# Main.net
KiCad netlist of a schematic drawn in Altium Designer
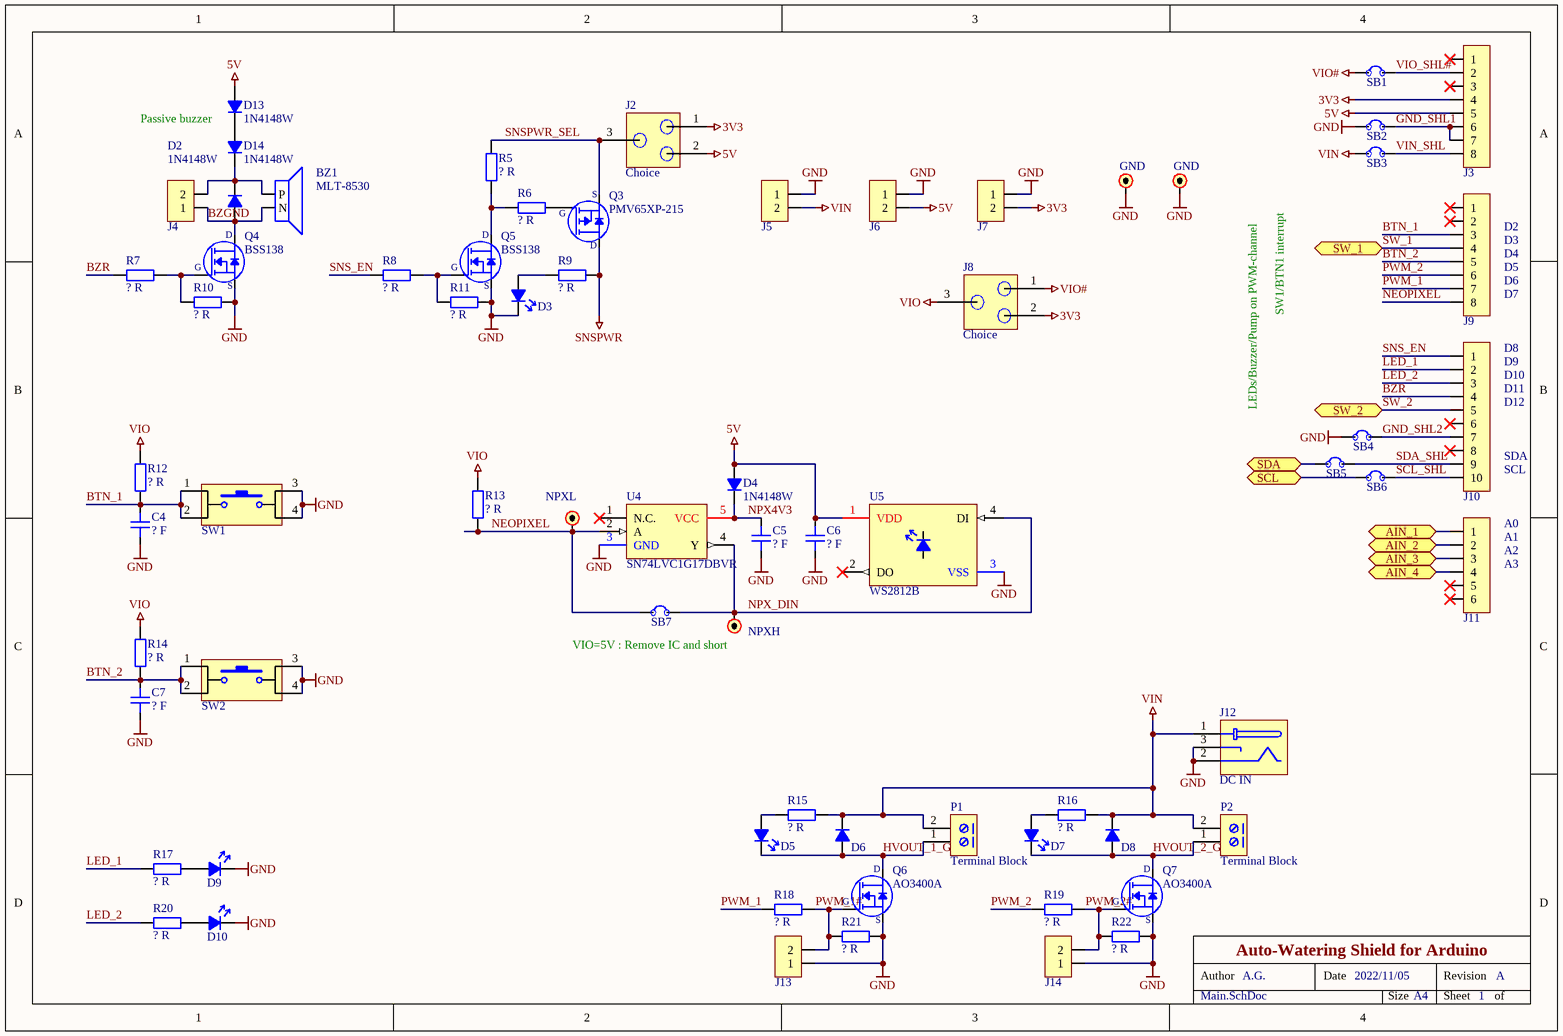
[diagram p0: Main.SchDoc]

(export (version "E")
  (design (tool "Eeschema 10.0.6"))
  (components
    (comp (ref "BZ1")
      (value "MLT-8530")
      (footprint "MLT-8530")
      (description "Magnetic Buzzer SMD 8.5x3.3 Passive 2.5V~4.5V")
      (fields (field (name "MANUFACTURER") "Jiangsu Huaneng Elec"))
      (libsource (lib "Buzzer") (part "MLT-8530"))
    )
    (comp (ref "C4")
      (value "? F")
      (footprint "0603C_RF_M")
      (description "Capacitor")
      (fields (field (name "TOLERANCE") "?") (field (name "MANUFACTURER") "Generic Brand"))
      (libsource (lib "AG.Generic") (part "C"))
    )
    (comp (ref "C5")
      (value "? F")
      (footprint "0603C_RF_M")
      (description "Capacitor")
      (fields (field (name "TOLERANCE") "?") (field (name "MANUFACTURER") "Generic Brand"))
      (libsource (lib "AG.Generic") (part "C"))
    )
    (comp (ref "C6")
      (value "? F")
      (footprint "0603C_RF_M")
      (description "Capacitor")
      (fields (field (name "TOLERANCE") "?") (field (name "MANUFACTURER") "Generic Brand"))
      (libsource (lib "AG.Generic") (part "C"))
    )
    (comp (ref "C7")
      (value "? F")
      (footprint "0603C_RF_M")
      (description "Capacitor")
      (fields (field (name "TOLERANCE") "?") (field (name "MANUFACTURER") "Generic Brand"))
      (libsource (lib "AG.Generic") (part "C"))
    )
    (comp (ref "D2")
      (value "1N4148W")
      (footprint "D_SOD-123")
      (description "DIODE GEN PURP 100V 300MA SOD123")
      (fields (field (name "SIMILAR PART") "BAV16W") (field (name "MANUFACTURER") "Diodes Incorporated"))
      (libsource (lib "Diode") (part "1N4148W"))
    )
    (comp (ref "D3")
      (value "Unspecified")
      (footprint "0805LED_RF_M")
      (description "LED")
      (fields (field (name "MANUFACTURER") "Generic Brand"))
      (libsource (lib "AG.Generic") (part "LED"))
    )
    (comp (ref "D4")
      (value "1N4148W")
      (footprint "D_SOD-123")
      (description "DIODE GEN PURP 100V 300MA SOD123")
      (fields (field (name "SIMILAR PART") "BAV16W") (field (name "MANUFACTURER") "Diodes Incorporated"))
      (libsource (lib "Diode") (part "1N4148W"))
    )
    (comp (ref "D5")
      (value "Unspecified")
      (footprint "0805LED_RF_M")
      (description "LED")
      (fields (field (name "MANUFACTURER") "Generic Brand"))
      (libsource (lib "AG.Generic") (part "LED"))
    )
    (comp (ref "D6")
      (value "D")
      (footprint "ONSEMI_DO214AC_RF_M")
      (description "Diode (Rectifier)")
      (fields (field (name "MANUFACTURER") "Generic Brand"))
      (libsource (lib "AG.Generic") (part "D"))
    )
    (comp (ref "D7")
      (value "Unspecified")
      (footprint "0805LED_RF_M")
      (description "LED")
      (fields (field (name "MANUFACTURER") "Generic Brand"))
      (libsource (lib "AG.Generic") (part "LED"))
    )
    (comp (ref "D8")
      (value "D")
      (footprint "ONSEMI_DO214AC_RF_M")
      (description "Diode (Rectifier)")
      (fields (field (name "MANUFACTURER") "Generic Brand"))
      (libsource (lib "AG.Generic") (part "D"))
    )
    (comp (ref "D9")
      (value "Unspecified")
      (footprint "0805LED_RF_M")
      (description "LED")
      (fields (field (name "MANUFACTURER") "Generic Brand"))
      (libsource (lib "AG.Generic") (part "LED"))
    )
    (comp (ref "D10")
      (value "Unspecified")
      (footprint "0805LED_RF_M")
      (description "LED")
      (fields (field (name "MANUFACTURER") "Generic Brand"))
      (libsource (lib "AG.Generic") (part "LED"))
    )
    (comp (ref "D13")
      (value "1N4148W")
      (footprint "D_SOD-123")
      (description "DIODE GEN PURP 100V 300MA SOD123")
      (fields (field (name "SIMILAR PART") "BAV16W") (field (name "MANUFACTURER") "Diodes Incorporated"))
      (libsource (lib "Diode") (part "1N4148W"))
    )
    (comp (ref "D14")
      (value "1N4148W")
      (footprint "D_SOD-123")
      (description "DIODE GEN PURP 100V 300MA SOD123")
      (fields (field (name "SIMILAR PART") "BAV16W") (field (name "MANUFACTURER") "Diodes Incorporated"))
      (libsource (lib "Diode") (part "1N4148W"))
    )
    (comp (ref "J2")
      (value "Choice")
      (footprint "AG.Misc:CHOICE_R0805_TR")
      (libsource (lib "AG.Misc") (part "Choice"))
    )
    (comp (ref "J3")
      (value "PINHDR-8P1")
      (footprint "PINHDR-8P1-2.54")
      (description "Pin Header Single Row 8 Positions")
      (libsource (lib "AG.Connectors") (part "PINHDR-8P1"))
    )
    (comp (ref "J4")
      (value "PINHDR-2P1")
      (footprint "HEADER-2.54-2P1")
      (description "Pin Header Single Row 2 Positions")
      (libsource (lib "") (part "PINHDR-2P1_1"))
    )
    (comp (ref "J5")
      (value "PINHDR-2P1")
      (footprint "HEADER-2.54-2P1")
      (description "Pin Header Single Row 2 Positions")
      (libsource (lib "AG.Connectors") (part "PINHDR-2P1"))
    )
    (comp (ref "J6")
      (value "PINHDR-2P1")
      (footprint "HEADER-2.54-2P1")
      (description "Pin Header Single Row 2 Positions")
      (libsource (lib "AG.Connectors") (part "PINHDR-2P1"))
    )
    (comp (ref "J7")
      (value "PINHDR-2P1")
      (footprint "HEADER-2.54-2P1")
      (description "Pin Header Single Row 2 Positions")
      (libsource (lib "AG.Connectors") (part "PINHDR-2P1"))
    )
    (comp (ref "J8")
      (value "Choice")
      (footprint "AG.Misc:CHOICE_R0805_TR")
      (libsource (lib "AG.Misc") (part "Choice"))
    )
    (comp (ref "J9")
      (value "PINHDR-8P1")
      (footprint "PINHDR-8P1-2.54")
      (description "Pin Header Single Row 8 Positions")
      (libsource (lib "AG.Connectors") (part "PINHDR-8P1"))
    )
    (comp (ref "J10")
      (value "PINHDR-10P1")
      (footprint "AG.Connectors:HEADER-2.54-10P1")
      (description "Generic Pin Header 10x1")
      (libsource (lib "AG.Connectors") (part "PINHDR-10P1"))
    )
    (comp (ref "J11")
      (value "PINHDR-6P1")
      (footprint "HEADER-2.54-6P1")
      (description "Pin Header Single Row 6 Positions")
      (libsource (lib "AG.Connectors") (part "PINHDR-6P1"))
    )
    (comp (ref "J12")
      (value "DC IN")
      (footprint "CON JACK PWR 2.5mm PJ-002BH - duplicate")
      (description "CONN PWR JACK 2.5X5.5MM SOLDER")
      (fields (field (name "MANUFACTURER") "CUI Devices") (field (name "PARTNO") "CP-002BH-ND"))
      (libsource (lib "AG.Connectors") (part "PJ-002BH"))
    )
    (comp (ref "J13")
      (value "PINHDR-2P1")
      (footprint "HEADER-2.54-2P1")
      (description "Pin Header Single Row 2 Positions")
      (libsource (lib "") (part "PINHDR-2P1_1"))
    )
    (comp (ref "J14")
      (value "PINHDR-2P1")
      (footprint "HEADER-2.54-2P1")
      (description "Pin Header Single Row 2 Positions")
      (libsource (lib "") (part "PINHDR-2P1_1"))
    )
    (comp (ref "P1")
      (value "Terminal Block")
      (footprint "AG.Connectors:KF128-2P")
      (libsource (lib "AG.Connectors") (part "TERM-BLOCK-2C"))
    )
    (comp (ref "P2")
      (value "Terminal Block")
      (footprint "AG.Connectors:KF128-2P")
      (libsource (lib "AG.Connectors") (part "TERM-BLOCK-2C"))
    )
    (comp (ref "Q3")
      (value "PMV65XP-215")
      (footprint "IRLML_SOT-23")
      (description "MOSFET P-CH 20V 2.8A 23SOT")
      (fields (field (name "ALTERNATIVE SUPPLIER PART NO") "9000037397"))
      (libsource (lib "AG.Discrete") (part "PMV65XP-215"))
    )
    (comp (ref "Q4")
      (value "BSS138")
      (footprint "IRLML_SOT-23")
      (description "MOSFET N-CH 50V 200MA SOT23")
      (fields
        (field (name "MANUFACTURER") "ON Semiconductor")
        (field (name "MANUFACTURER PART NO") "BSS138LT1G")
      )
      (libsource (lib "AG.Discrete") (part "BSS138"))
    )
    (comp (ref "Q5")
      (value "BSS138")
      (footprint "IRLML_SOT-23")
      (description "MOSFET N-CH 50V 200MA SOT23")
      (fields
        (field (name "MANUFACTURER") "ON Semiconductor")
        (field (name "MANUFACTURER PART NO") "BSS138LT1G")
      )
      (libsource (lib "AG.Discrete") (part "BSS138"))
    )
    (comp (ref "Q6")
      (value "AO3400A")
      (footprint "IRLML_SOT-23")
      (description "MOSFET N-CH 30V 5.7A SOT23-3L")
      (fields (field (name "MANUFACTURER") "Alpha & Omega"))
      (libsource (lib "AG.Discrete") (part "AO3400A"))
    )
    (comp (ref "Q7")
      (value "AO3400A")
      (footprint "IRLML_SOT-23")
      (description "MOSFET N-CH 30V 5.7A SOT23-3L")
      (fields (field (name "MANUFACTURER") "Alpha & Omega"))
      (libsource (lib "AG.Discrete") (part "AO3400A"))
    )
    (comp (ref "R5")
      (value "? R")
      (footprint "Chip:R0603_RF_M")
      (description "Resistor")
      (fields (field (name "TOLERANCE") "?") (field (name "MANUFACTURER") "Generic Brand"))
      (libsource (lib "AG.Generic") (part "R"))
    )
    (comp (ref "R6")
      (value "? R")
      (footprint "Chip:R0603_RF_M")
      (description "Resistor")
      (fields (field (name "TOLERANCE") "?") (field (name "MANUFACTURER") "Generic Brand"))
      (libsource (lib "AG.Generic") (part "R"))
    )
    (comp (ref "R7")
      (value "? R")
      (footprint "Chip:R0603_RF_M")
      (description "Resistor")
      (fields (field (name "TOLERANCE") "?") (field (name "MANUFACTURER") "Generic Brand"))
      (libsource (lib "AG.Generic") (part "R"))
    )
    (comp (ref "R8")
      (value "? R")
      (footprint "Chip:R0603_RF_M")
      (description "Resistor")
      (fields (field (name "TOLERANCE") "?") (field (name "MANUFACTURER") "Generic Brand"))
      (libsource (lib "AG.Generic") (part "R"))
    )
    (comp (ref "R9")
      (value "? R")
      (footprint "Chip:R0603_RF_M")
      (description "Resistor")
      (fields (field (name "TOLERANCE") "?") (field (name "MANUFACTURER") "Generic Brand"))
      (libsource (lib "AG.Generic") (part "R"))
    )
    (comp (ref "R10")
      (value "? R")
      (footprint "Chip:R0603_RF_M")
      (description "Resistor")
      (fields (field (name "TOLERANCE") "?") (field (name "MANUFACTURER") "Generic Brand"))
      (libsource (lib "AG.Generic") (part "R"))
    )
    (comp (ref "R11")
      (value "? R")
      (footprint "Chip:R0603_RF_M")
      (description "Resistor")
      (fields (field (name "TOLERANCE") "?") (field (name "MANUFACTURER") "Generic Brand"))
      (libsource (lib "AG.Generic") (part "R"))
    )
    (comp (ref "R12")
      (value "? R")
      (footprint "Chip:R0603_RF_M")
      (description "Resistor")
      (fields (field (name "TOLERANCE") "?") (field (name "MANUFACTURER") "Generic Brand"))
      (libsource (lib "AG.Generic") (part "R"))
    )
    (comp (ref "R13")
      (value "? R")
      (footprint "Chip:R0603_RF_M")
      (description "Resistor")
      (fields (field (name "TOLERANCE") "?") (field (name "MANUFACTURER") "Generic Brand"))
      (libsource (lib "AG.Generic") (part "R"))
    )
    (comp (ref "R14")
      (value "? R")
      (footprint "Chip:R0603_RF_M")
      (description "Resistor")
      (fields (field (name "TOLERANCE") "?") (field (name "MANUFACTURER") "Generic Brand"))
      (libsource (lib "AG.Generic") (part "R"))
    )
    (comp (ref "R15")
      (value "? R")
      (footprint "Chip:R0603_RF_M")
      (description "Resistor")
      (fields (field (name "TOLERANCE") "?") (field (name "MANUFACTURER") "Generic Brand"))
      (libsource (lib "AG.Generic") (part "R"))
    )
    (comp (ref "R16")
      (value "? R")
      (footprint "Chip:R0603_RF_M")
      (description "Resistor")
      (fields (field (name "TOLERANCE") "?") (field (name "MANUFACTURER") "Generic Brand"))
      (libsource (lib "AG.Generic") (part "R"))
    )
    (comp (ref "R17")
      (value "? R")
      (footprint "Chip:R0603_RF_M")
      (description "Resistor")
      (fields (field (name "TOLERANCE") "?") (field (name "MANUFACTURER") "Generic Brand"))
      (libsource (lib "AG.Generic") (part "R"))
    )
    (comp (ref "R18")
      (value "? R")
      (footprint "Chip:R0603_RF_M")
      (description "Resistor")
      (fields (field (name "TOLERANCE") "?") (field (name "MANUFACTURER") "Generic Brand"))
      (libsource (lib "AG.Generic") (part "R"))
    )
    (comp (ref "R19")
      (value "? R")
      (footprint "Chip:R0603_RF_M")
      (description "Resistor")
      (fields (field (name "TOLERANCE") "?") (field (name "MANUFACTURER") "Generic Brand"))
      (libsource (lib "AG.Generic") (part "R"))
    )
    (comp (ref "R20")
      (value "? R")
      (footprint "Chip:R0603_RF_M")
      (description "Resistor")
      (fields (field (name "TOLERANCE") "?") (field (name "MANUFACTURER") "Generic Brand"))
      (libsource (lib "AG.Generic") (part "R"))
    )
    (comp (ref "R21")
      (value "? R")
      (footprint "Chip:R0603_RF_M")
      (description "Resistor")
      (fields (field (name "TOLERANCE") "?") (field (name "MANUFACTURER") "Generic Brand"))
      (libsource (lib "AG.Generic") (part "R"))
    )
    (comp (ref "R22")
      (value "? R")
      (footprint "Chip:R0603_RF_M")
      (description "Resistor")
      (fields (field (name "TOLERANCE") "?") (field (name "MANUFACTURER") "Generic Brand"))
      (libsource (lib "AG.Generic") (part "R"))
    )
    (comp (ref "SB1")
      (value "Solder Bridge")
      (footprint "AG.Misc:SLDR_BRDG_0603_OPEN")
      (libsource (lib "AG.Misc") (part "Solder Bridge"))
    )
    (comp (ref "SB2")
      (value "Solder Bridge")
      (footprint "AG.Misc:SLDR_BRDG_0603_OPEN")
      (libsource (lib "AG.Misc") (part "Solder Bridge"))
    )
    (comp (ref "SB3")
      (value "Solder Bridge")
      (footprint "AG.Misc:SLDR_BRDG_0603_OPEN")
      (libsource (lib "AG.Misc") (part "Solder Bridge"))
    )
    (comp (ref "SB4")
      (value "Solder Bridge")
      (footprint "AG.Misc:SLDR_BRDG_0603_OPEN")
      (libsource (lib "AG.Misc") (part "Solder Bridge"))
    )
    (comp (ref "SB5")
      (value "Solder Bridge")
      (footprint "AG.Misc:SLDR_BRDG_0603_OPEN")
      (libsource (lib "AG.Misc") (part "Solder Bridge"))
    )
    (comp (ref "SB6")
      (value "Solder Bridge")
      (footprint "AG.Misc:SLDR_BRDG_0603_OPEN")
      (libsource (lib "AG.Misc") (part "Solder Bridge"))
    )
    (comp (ref "SB7")
      (value "Solder Bridge")
      (footprint "AG.Misc:SLDR_BRDG_0603_OPEN")
      (libsource (lib "AG.Misc") (part "Solder Bridge"))
    )
    (comp (ref "SW1")
      (value "BTN-SPST-NO-4C")
      (footprint "AG.Electromechanical:SW_TL3305AF160QG")
      (description "Tactile Switch SPST-NO")
      (fields (field (name "MANUFACTURER") "Generic Brand"))
      (libsource (lib "AG.Generic") (part "BTN-SPST-NO-4C"))
    )
    (comp (ref "SW2")
      (value "BTN-SPST-NO-4C")
      (footprint "AG.Electromechanical:SW_TL3305AF160QG")
      (description "Tactile Switch SPST-NO")
      (fields (field (name "MANUFACTURER") "Generic Brand"))
      (libsource (lib "AG.Generic") (part "BTN-SPST-NO-4C"))
    )
    (comp (ref "TP5")
      (value "GND")
      (footprint "PAD_R_1.5MM")
      (description "Test Point / Pad")
      (libsource (lib "AG.Misc") (part "Test Point"))
    )
    (comp (ref "TP6")
      (value "GND")
      (footprint "PAD_R_1.5MM")
      (description "Test Point / Pad")
      (libsource (lib "AG.Misc") (part "Test Point"))
    )
    (comp (ref "TP7")
      (value "NPXL")
      (footprint "PAD_R_1MM")
      (description "Test Point / Pad")
      (libsource (lib "AG.Misc") (part "Test Point"))
    )
    (comp (ref "TP8")
      (value "NPXH")
      (footprint "PAD_R_1MM")
      (description "Test Point / Pad")
      (libsource (lib "AG.Misc") (part "Test Point"))
    )
    (comp (ref "U4")
      (value "SN74LVC1G17DBVR")
      (footprint "TI_SOT-23-5")
      (description "IC BUF NON-INVERT 5.5V SOT23-5")
      (fields (field (name "MANUFACTURER") "Texas Instruments"))
      (libsource (lib "AG.IC") (part "SN74LVC1G17DBVR"))
    )
    (comp (ref "U5")
      (value "WS2812B")
      (footprint "WS2812B")
      (description "ADDRESS LED DISCRETE SERIAL RGB")
      (fields (field (name "MANUFACTURER") "Worldsemi"))
      (libsource (lib "AG.Discrete") (part "WS2812B"))
    )
  )
  (nets
    (net (code "1") (name "/AIN_1") (class "Default")
      (node (ref "J11") (pin "1") (pinfunction "1_1") (pintype "passive"))
    )
    (net (code "2") (name "/AIN_2") (class "Default")
      (node (ref "J11") (pin "2") (pinfunction "2_2") (pintype "passive"))
    )
    (net (code "3") (name "/AIN_3") (class "Default")
      (node (ref "J11") (pin "3") (pinfunction "3_3") (pintype "passive"))
    )
    (net (code "4") (name "/AIN_4") (class "Default")
      (node (ref "J11") (pin "4") (pinfunction "4_4") (pintype "passive"))
    )
    (net (code "5") (name "/BTN_1") (class "Default")
      (node (ref "C4") (pin "2") (pinfunction "2_2") (pintype "passive"))
      (node (ref "J9") (pin "3") (pinfunction "3_3") (pintype "passive"))
      (node (ref "R12") (pin "1") (pintype "passive"))
      (node (ref "SW1") (pin "1") (pinfunction "1_1") (pintype "passive"))
      (node (ref "SW1") (pin "2") (pinfunction "2_2") (pintype "passive"))
    )
    (net (code "6") (name "/BTN_2") (class "Default")
      (node (ref "C7") (pin "2") (pinfunction "2_2") (pintype "passive"))
      (node (ref "J9") (pin "5") (pinfunction "5_5") (pintype "passive"))
      (node (ref "R14") (pin "1") (pintype "passive"))
      (node (ref "SW2") (pin "1") (pinfunction "1_1") (pintype "passive"))
      (node (ref "SW2") (pin "2") (pinfunction "2_2") (pintype "passive"))
    )
    (net (code "7") (name "/BZGND") (class "Default")
      (node (ref "BZ1") (pin "N") (pinfunction "N_N") (pintype "power_in"))
      (node (ref "D2") (pin "A") (pinfunction "A_A") (pintype "passive"))
      (node (ref "J4") (pin "1") (pinfunction "1_1") (pintype "passive"))
      (node (ref "Q4") (pin "3") (pinfunction "D_3") (pintype "passive"))
    )
    (net (code "8") (name "/BZR") (class "Default")
      (node (ref "J10") (pin "4") (pinfunction "4_4") (pintype "passive"))
      (node (ref "R7") (pin "1") (pintype "passive"))
    )
    (net (code "9") (name "/GND_SHL1") (class "Default")
      (node (ref "J3") (pin "6") (pinfunction "6_6") (pintype "passive"))
      (node (ref "J3") (pin "7") (pinfunction "7_7") (pintype "passive"))
      (node (ref "SB2") (pin "2") (pinfunction "2_2") (pintype "passive"))
    )
    (net (code "10") (name "/GND_SHL2") (class "Default")
      (node (ref "J10") (pin "7") (pinfunction "7_7") (pintype "passive"))
      (node (ref "SB4") (pin "2") (pinfunction "2_2") (pintype "passive"))
    )
    (net (code "11") (name "/HVOUT_1_GND") (class "Default")
      (node (ref "D5") (pin "C") (pinfunction "C_C") (pintype "passive"))
      (node (ref "D6") (pin "A") (pinfunction "A_A") (pintype "passive"))
      (node (ref "P1") (pin "1") (pinfunction "1_1") (pintype "passive"))
      (node (ref "Q6") (pin "3") (pinfunction "D_3") (pintype "passive"))
    )
    (net (code "12") (name "/HVOUT_2_GND") (class "Default")
      (node (ref "D7") (pin "C") (pinfunction "C_C") (pintype "passive"))
      (node (ref "D8") (pin "A") (pinfunction "A_A") (pintype "passive"))
      (node (ref "P2") (pin "1") (pinfunction "1_1") (pintype "passive"))
      (node (ref "Q7") (pin "3") (pinfunction "D_3") (pintype "passive"))
    )
    (net (code "13") (name "/LED_1") (class "Default")
      (node (ref "J10") (pin "2") (pinfunction "2_2") (pintype "passive"))
      (node (ref "R17") (pin "1") (pintype "passive"))
    )
    (net (code "14") (name "/LED_2") (class "Default")
      (node (ref "J10") (pin "3") (pinfunction "3_3") (pintype "passive"))
      (node (ref "R20") (pin "1") (pintype "passive"))
    )
    (net (code "15") (name "/NEOPIXEL") (class "Default")
      (node (ref "J9") (pin "8") (pinfunction "8_8") (pintype "passive"))
      (node (ref "R13") (pin "2") (pintype "passive"))
      (node (ref "SB7") (pin "1") (pinfunction "1_1") (pintype "passive"))
      (node (ref "TP7") (pin "1") (pinfunction "1_1") (pintype "passive"))
      (node (ref "U4") (pin "2") (pinfunction "A_2") (pintype "input"))
    )
    (net (code "16") (name "/NPX4V3") (class "Default")
      (node (ref "C5") (pin "1") (pinfunction "1_1") (pintype "passive"))
      (node (ref "D4") (pin "C") (pinfunction "C_C") (pintype "passive"))
      (node (ref "U4") (pin "5") (pinfunction "VCC_5") (pintype "power_in"))
    )
    (net (code "17") (name "/NPX_DIN") (class "Default")
      (node (ref "SB7") (pin "2") (pinfunction "2_2") (pintype "passive"))
      (node (ref "TP8") (pin "1") (pinfunction "1_1") (pintype "passive"))
      (node (ref "U4") (pin "4") (pinfunction "Y_4") (pintype "output"))
      (node (ref "U5") (pin "4") (pinfunction "DI_4") (pintype "input"))
    )
    (net (code "18") (name "/PWM_1") (class "Default")
      (node (ref "J9") (pin "7") (pinfunction "7_7") (pintype "passive"))
      (node (ref "R18") (pin "1") (pintype "passive"))
    )
    (net (code "19") (name "/PWM_1#") (class "Default")
      (node (ref "J13") (pin "2") (pinfunction "2_2") (pintype "passive"))
      (node (ref "Q6") (pin "1") (pinfunction "G_1") (pintype "passive"))
      (node (ref "R18") (pin "2") (pintype "passive"))
      (node (ref "R21") (pin "2") (pintype "passive"))
    )
    (net (code "20") (name "/PWM_2") (class "Default")
      (node (ref "J9") (pin "6") (pinfunction "6_6") (pintype "passive"))
      (node (ref "R19") (pin "1") (pintype "passive"))
    )
    (net (code "21") (name "/PWM_2#") (class "Default")
      (node (ref "J14") (pin "2") (pinfunction "2_2") (pintype "passive"))
      (node (ref "Q7") (pin "1") (pinfunction "G_1") (pintype "passive"))
      (node (ref "R19") (pin "2") (pintype "passive"))
      (node (ref "R22") (pin "2") (pintype "passive"))
    )
    (net (code "22") (name "/SCL") (class "Default")
      (node (ref "SB6") (pin "1") (pinfunction "1_1") (pintype "passive"))
    )
    (net (code "23") (name "/SCL_SHL") (class "Default")
      (node (ref "J10") (pin "10") (pinfunction "10_10") (pintype "passive"))
      (node (ref "SB6") (pin "2") (pinfunction "2_2") (pintype "passive"))
    )
    (net (code "24") (name "/SDA") (class "Default")
      (node (ref "SB5") (pin "1") (pinfunction "1_1") (pintype "passive"))
    )
    (net (code "25") (name "/SDA_SHL") (class "Default")
      (node (ref "J10") (pin "9") (pinfunction "9_9") (pintype "passive"))
      (node (ref "SB5") (pin "2") (pinfunction "2_2") (pintype "passive"))
    )
    (net (code "26") (name "/SNSPWR_SEL") (class "Default")
      (node (ref "J2") (pin "3") (pinfunction "3_3") (pintype "passive"))
      (node (ref "Q3") (pin "2") (pinfunction "Source_2") (pintype "passive"))
      (node (ref "R5") (pin "1") (pintype "passive"))
    )
    (net (code "27") (name "/SNS_EN") (class "Default")
      (node (ref "J10") (pin "1") (pinfunction "1_1") (pintype "passive"))
      (node (ref "R8") (pin "1") (pintype "passive"))
    )
    (net (code "28") (name "/SW_1") (class "Default")
      (node (ref "J9") (pin "4") (pinfunction "4_4") (pintype "passive"))
    )
    (net (code "29") (name "/SW_2") (class "Default")
      (node (ref "J10") (pin "5") (pinfunction "5_5") (pintype "passive"))
    )
    (net (code "30") (name "/VIN_SHL") (class "Default")
      (node (ref "J3") (pin "8") (pinfunction "8_8") (pintype "passive"))
      (node (ref "SB3") (pin "2") (pinfunction "2_2") (pintype "passive"))
    )
    (net (code "31") (name "/VIO_SHL#") (class "Default")
      (node (ref "J3") (pin "2") (pinfunction "2_2") (pintype "passive"))
      (node (ref "SB1") (pin "2") (pinfunction "2_2") (pintype "passive"))
    )
    (net (code "32") (name "3V3") (class "Default")
      (node (ref "J2") (pin "1") (pinfunction "1_1") (pintype "passive"))
      (node (ref "J3") (pin "4") (pinfunction "4_4") (pintype "passive"))
      (node (ref "J7") (pin "2") (pinfunction "2_2") (pintype "passive"))
      (node (ref "J8") (pin "2") (pinfunction "2_2") (pintype "passive"))
    )
    (net (code "33") (name "5V") (class "Default")
      (node (ref "C6") (pin "1") (pinfunction "1_1") (pintype "passive"))
      (node (ref "D13") (pin "A") (pinfunction "A_A") (pintype "passive"))
      (node (ref "D4") (pin "A") (pinfunction "A_A") (pintype "passive"))
      (node (ref "J2") (pin "2") (pinfunction "2_2") (pintype "passive"))
      (node (ref "J3") (pin "5") (pinfunction "5_5") (pintype "passive"))
      (node (ref "J6") (pin "2") (pinfunction "2_2") (pintype "passive"))
      (node (ref "U5") (pin "1") (pinfunction "VDD_1") (pintype "power_in"))
    )
    (net (code "34") (name "GND") (class "Default")
      (node (ref "C4") (pin "1") (pinfunction "1_1") (pintype "passive"))
      (node (ref "C5") (pin "2") (pinfunction "2_2") (pintype "passive"))
      (node (ref "C6") (pin "2") (pinfunction "2_2") (pintype "passive"))
      (node (ref "C7") (pin "1") (pinfunction "1_1") (pintype "passive"))
      (node (ref "D10") (pin "C") (pinfunction "C_C") (pintype "passive"))
      (node (ref "D3") (pin "C") (pinfunction "C_C") (pintype "passive"))
      (node (ref "D9") (pin "C") (pinfunction "C_C") (pintype "passive"))
      (node (ref "J12") (pin "2") (pinfunction "2_2") (pintype "passive"))
      (node (ref "J12") (pin "3") (pinfunction "3_3") (pintype "passive"))
      (node (ref "J13") (pin "1") (pinfunction "1_1") (pintype "passive"))
      (node (ref "J14") (pin "1") (pinfunction "1_1") (pintype "passive"))
      (node (ref "J5") (pin "1") (pinfunction "1_1") (pintype "passive"))
      (node (ref "J6") (pin "1") (pinfunction "1_1") (pintype "passive"))
      (node (ref "J7") (pin "1") (pinfunction "1_1") (pintype "passive"))
      (node (ref "Q4") (pin "2") (pinfunction "S_2") (pintype "passive"))
      (node (ref "Q5") (pin "2") (pinfunction "S_2") (pintype "passive"))
      (node (ref "Q6") (pin "2") (pinfunction "S_2") (pintype "passive"))
      (node (ref "Q7") (pin "2") (pinfunction "S_2") (pintype "passive"))
      (node (ref "R10") (pin "1") (pintype "passive"))
      (node (ref "R11") (pin "1") (pintype "passive"))
      (node (ref "R21") (pin "1") (pintype "passive"))
      (node (ref "R22") (pin "1") (pintype "passive"))
      (node (ref "SB2") (pin "1") (pinfunction "1_1") (pintype "passive"))
      (node (ref "SB4") (pin "1") (pinfunction "1_1") (pintype "passive"))
      (node (ref "SW1") (pin "3") (pinfunction "3_3") (pintype "passive"))
      (node (ref "SW1") (pin "4") (pinfunction "4_4") (pintype "passive"))
      (node (ref "SW2") (pin "3") (pinfunction "3_3") (pintype "passive"))
      (node (ref "SW2") (pin "4") (pinfunction "4_4") (pintype "passive"))
      (node (ref "TP5") (pin "1") (pinfunction "1_1") (pintype "passive"))
      (node (ref "TP6") (pin "1") (pinfunction "1_1") (pintype "passive"))
      (node (ref "U4") (pin "3") (pinfunction "GND_3") (pintype "power_in"))
      (node (ref "U5") (pin "3") (pinfunction "VSS_3") (pintype "power_in"))
    )
    (net (code "35") (name "Net-(BZ1-PadP)") (class "Default")
      (node (ref "BZ1") (pin "P") (pinfunction "P_P") (pintype "power_in"))
      (node (ref "D14") (pin "C") (pinfunction "C_C") (pintype "passive"))
      (node (ref "D2") (pin "C") (pinfunction "C_C") (pintype "passive"))
      (node (ref "J4") (pin "2") (pinfunction "2_2") (pintype "passive"))
    )
    (net (code "36") (name "Net-(D3-PadA)") (class "Default")
      (node (ref "D3") (pin "A") (pinfunction "A_A") (pintype "passive"))
      (node (ref "R9") (pin "1") (pintype "passive"))
    )
    (net (code "37") (name "Net-(D5-PadA)") (class "Default")
      (node (ref "D5") (pin "A") (pinfunction "A_A") (pintype "passive"))
      (node (ref "R15") (pin "1") (pintype "passive"))
    )
    (net (code "38") (name "Net-(D7-PadA)") (class "Default")
      (node (ref "D7") (pin "A") (pinfunction "A_A") (pintype "passive"))
      (node (ref "R16") (pin "1") (pintype "passive"))
    )
    (net (code "39") (name "Net-(D9-PadA)") (class "Default")
      (node (ref "D9") (pin "A") (pinfunction "A_A") (pintype "passive"))
      (node (ref "R17") (pin "2") (pintype "passive"))
    )
    (net (code "40") (name "Net-(D10-PadA)") (class "Default")
      (node (ref "D10") (pin "A") (pinfunction "A_A") (pintype "passive"))
      (node (ref "R20") (pin "2") (pintype "passive"))
    )
    (net (code "41") (name "Net-(D13-PadC)") (class "Default")
      (node (ref "D13") (pin "C") (pinfunction "C_C") (pintype "passive"))
      (node (ref "D14") (pin "A") (pinfunction "A_A") (pintype "passive"))
    )
    (net (code "42") (name "Net-(Q3-Gate)") (class "Default")
      (node (ref "Q3") (pin "1") (pinfunction "Gate_1") (pintype "passive"))
      (node (ref "R6") (pin "2") (pintype "passive"))
    )
    (net (code "43") (name "Net-(Q4-G)") (class "Default")
      (node (ref "Q4") (pin "1") (pinfunction "G_1") (pintype "passive"))
      (node (ref "R10") (pin "2") (pintype "passive"))
      (node (ref "R7") (pin "2") (pintype "passive"))
    )
    (net (code "44") (name "Net-(Q5-D)") (class "Default")
      (node (ref "Q5") (pin "3") (pinfunction "D_3") (pintype "passive"))
      (node (ref "R5") (pin "2") (pintype "passive"))
      (node (ref "R6") (pin "1") (pintype "passive"))
    )
    (net (code "45") (name "Net-(Q5-G)") (class "Default")
      (node (ref "Q5") (pin "1") (pinfunction "G_1") (pintype "passive"))
      (node (ref "R11") (pin "2") (pintype "passive"))
      (node (ref "R8") (pin "2") (pintype "passive"))
    )
    (net (code "46") (name "SNSPWR") (class "Default")
      (node (ref "Q3") (pin "3") (pinfunction "Drain_3") (pintype "passive"))
      (node (ref "R9") (pin "2") (pintype "passive"))
    )
    (net (code "47") (name "VIN") (class "Default")
      (node (ref "D6") (pin "C") (pinfunction "C_C") (pintype "passive"))
      (node (ref "D8") (pin "C") (pinfunction "C_C") (pintype "passive"))
      (node (ref "J12") (pin "1") (pinfunction "1_1") (pintype "passive"))
      (node (ref "J5") (pin "2") (pinfunction "2_2") (pintype "passive"))
      (node (ref "P1") (pin "2") (pinfunction "2_2") (pintype "passive"))
      (node (ref "P2") (pin "2") (pinfunction "2_2") (pintype "passive"))
      (node (ref "R15") (pin "2") (pintype "passive"))
      (node (ref "R16") (pin "2") (pintype "passive"))
      (node (ref "SB3") (pin "1") (pinfunction "1_1") (pintype "passive"))
    )
    (net (code "48") (name "VIO") (class "Default")
      (node (ref "J8") (pin "3") (pinfunction "3_3") (pintype "passive"))
      (node (ref "R12") (pin "2") (pintype "passive"))
      (node (ref "R13") (pin "1") (pintype "passive"))
      (node (ref "R14") (pin "2") (pintype "passive"))
    )
    (net (code "49") (name "VIO#") (class "Default")
      (node (ref "J8") (pin "1") (pinfunction "1_1") (pintype "passive"))
      (node (ref "SB1") (pin "1") (pinfunction "1_1") (pintype "passive"))
    )
    (net (code "50") (name "unconnected-(J3-Pad1)") (class "Default")
      (node (ref "J3") (pin "1") (pinfunction "1_1") (pintype "passive+no_connect"))
    )
    (net (code "51") (name "unconnected-(J3-Pad3)") (class "Default")
      (node (ref "J3") (pin "3") (pinfunction "3_3") (pintype "passive+no_connect"))
    )
    (net (code "52") (name "unconnected-(J9-Pad1)") (class "Default")
      (node (ref "J9") (pin "1") (pinfunction "1_1") (pintype "passive+no_connect"))
    )
    (net (code "53") (name "unconnected-(J9-Pad2)") (class "Default")
      (node (ref "J9") (pin "2") (pinfunction "2_2") (pintype "passive+no_connect"))
    )
    (net (code "54") (name "unconnected-(J10-Pad6)") (class "Default")
      (node (ref "J10") (pin "6") (pinfunction "6_6") (pintype "passive+no_connect"))
    )
    (net (code "55") (name "unconnected-(J10-Pad8)") (class "Default")
      (node (ref "J10") (pin "8") (pinfunction "8_8") (pintype "passive+no_connect"))
    )
    (net (code "56") (name "unconnected-(J11-Pad5)") (class "Default")
      (node (ref "J11") (pin "5") (pinfunction "5_5") (pintype "passive+no_connect"))
    )
    (net (code "57") (name "unconnected-(J11-Pad6)") (class "Default")
      (node (ref "J11") (pin "6") (pinfunction "6_6") (pintype "passive+no_connect"))
    )
    (net (code "58") (name "unconnected-(U4-N.C.-Pad1)") (class "Default")
      (node (ref "U4") (pin "1") (pinfunction "N.C._1") (pintype "passive+no_connect"))
    )
    (net (code "59") (name "unconnected-(U5-DO-Pad2)") (class "Default")
      (node (ref "U5") (pin "2") (pinfunction "DO_2") (pintype "output+no_connect"))
    )
  )
)
